# HenHouseController.net
KiCad netlist of a schematic drawn in EAGLE
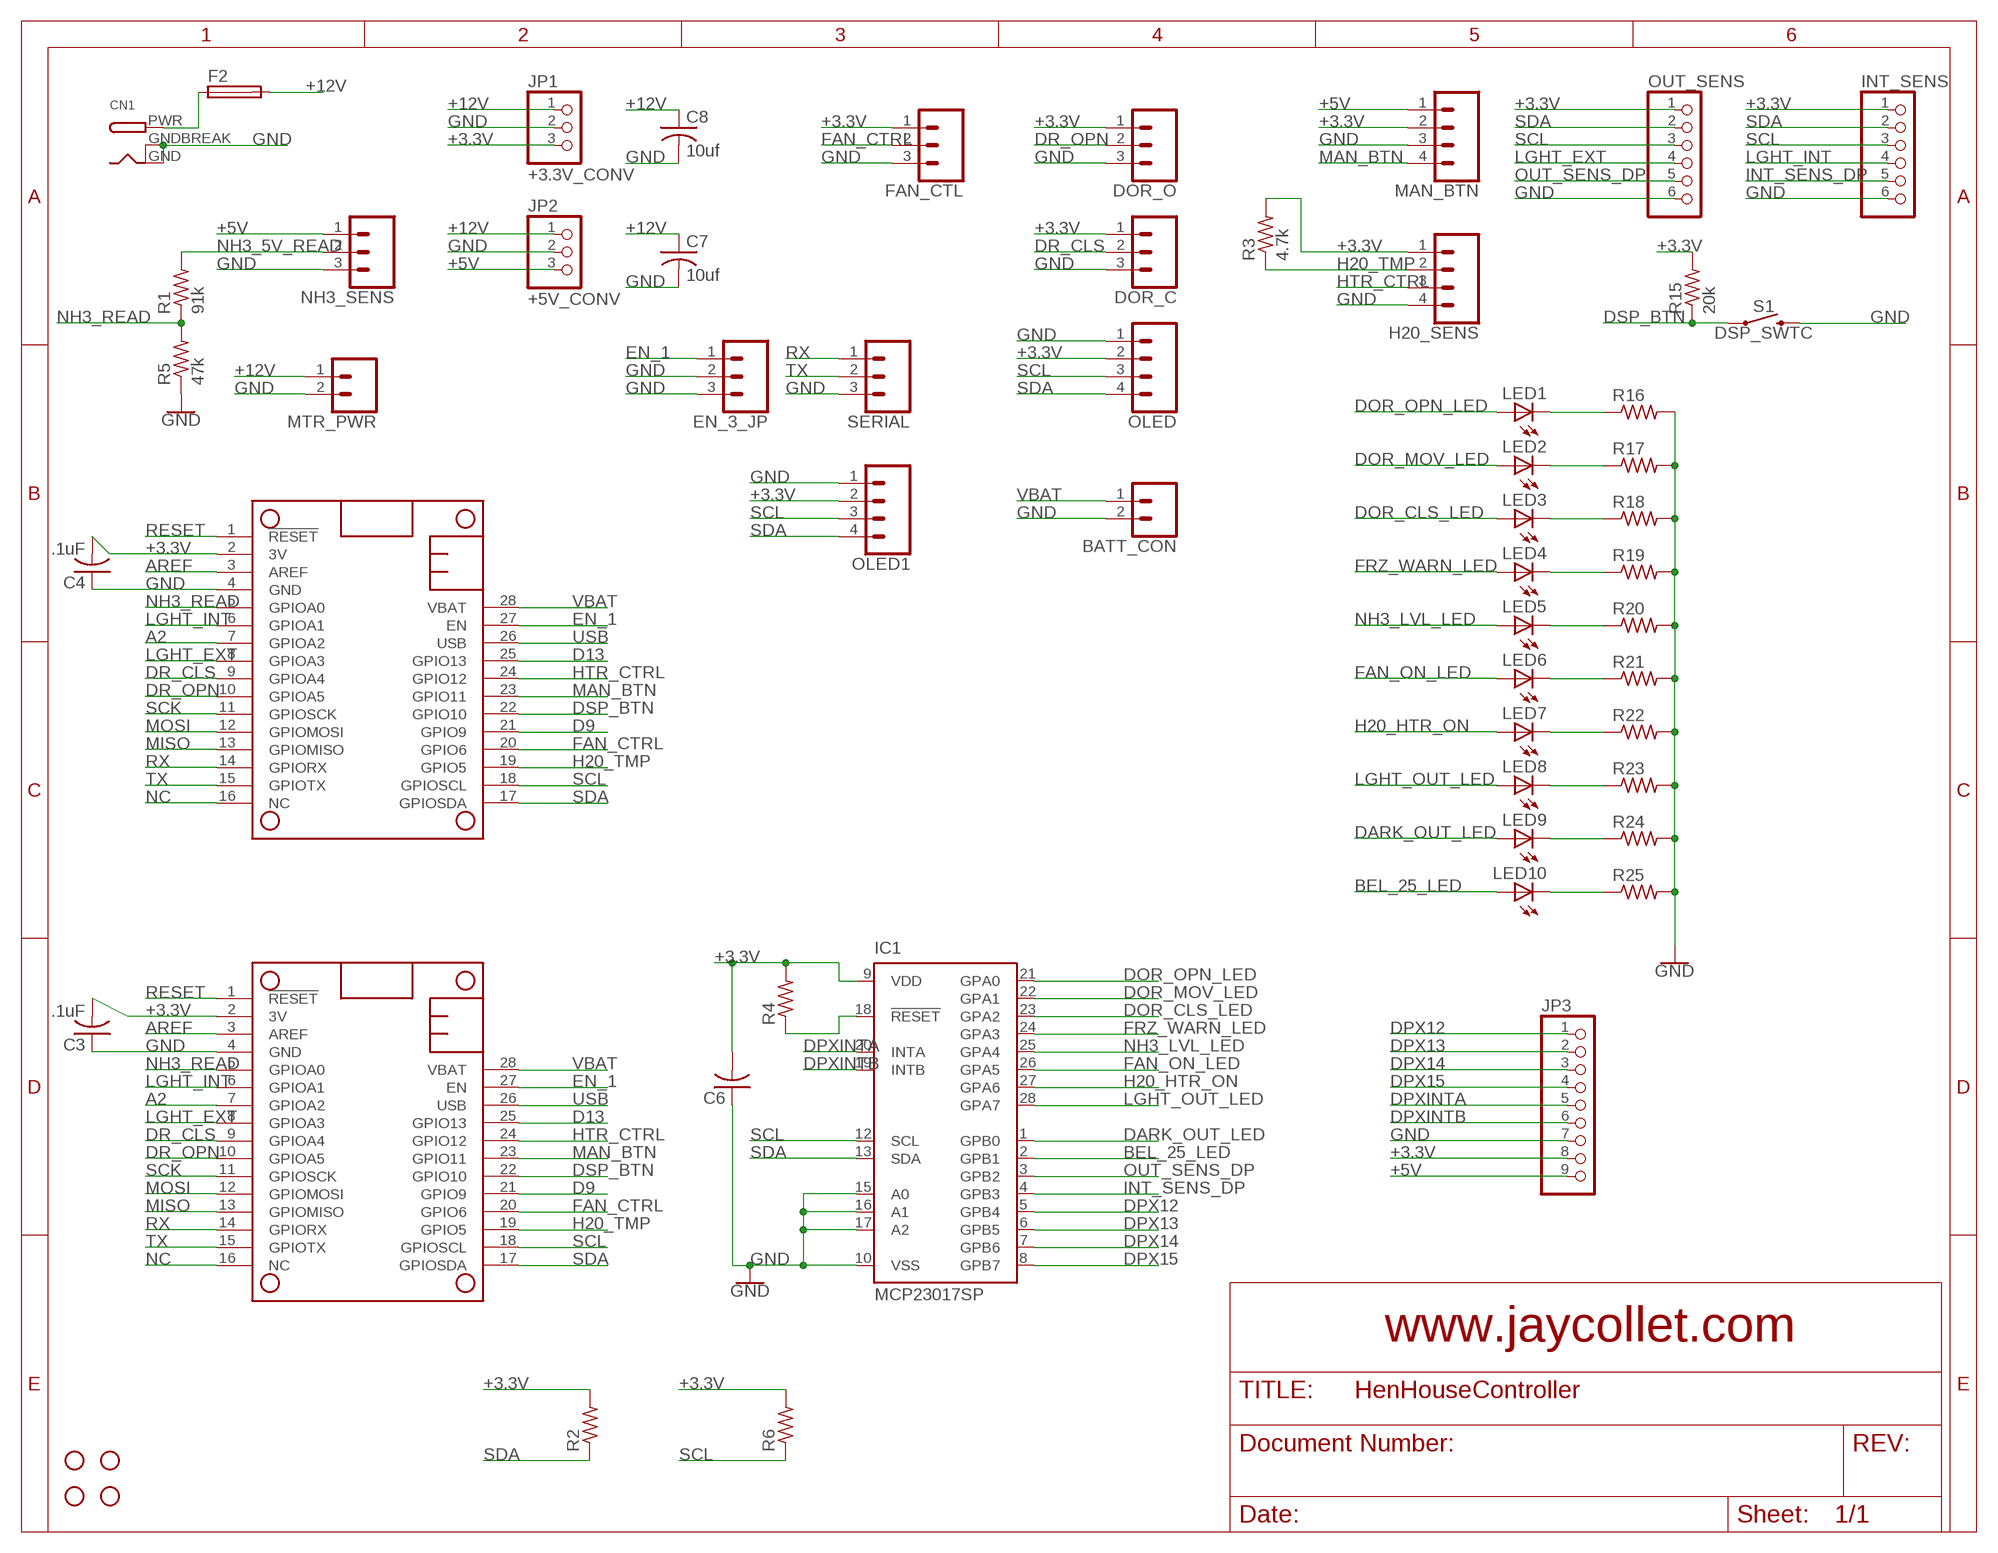
[diagram p0: schematic, sheet 1]

(export (version "E")
  (design (tool "Eeschema 10.0.6"))
  (components
    (comp (ref "BATT_CON")
      (value "CONN_02")
      (footprint "eagle-import:1X02")
      (libsource (lib "eagle-import") (part "CONN_02"))
    )
    (comp (ref "C3")
      (value ".1uF")
      (footprint "eagle-import:C0805")
      (libsource (lib "eagle-import") (part "C-USC0805"))
    )
    (comp (ref "C4")
      (value ".1uF")
      (footprint "eagle-import:C0805")
      (libsource (lib "eagle-import") (part "C-USC0805"))
    )
    (comp (ref "C6")
      (value "C-USC0805")
      (footprint "eagle-import:C0805")
      (libsource (lib "eagle-import") (part "C-USC0805"))
    )
    (comp (ref "C7")
      (value "10uf")
      (footprint "eagle-import:C0805")
      (libsource (lib "eagle-import") (part "C-USC0805"))
    )
    (comp (ref "C8")
      (value "10uf")
      (footprint "eagle-import:C0805")
      (libsource (lib "eagle-import") (part "C-USC0805"))
    )
    (comp (ref "CN1")
      (value "DCBARRELPTH")
      (footprint "eagle-import:DCJACK_2MM_PTH")
      (libsource (lib "eagle-import") (part "DCBARRELPTH"))
    )
    (comp (ref "DOR_C")
      (value "CONN_03")
      (footprint "eagle-import:1X03")
      (libsource (lib "eagle-import") (part "CONN_03"))
    )
    (comp (ref "DOR_O")
      (value "CONN_03")
      (footprint "eagle-import:1X03")
      (libsource (lib "eagle-import") (part "CONN_03"))
    )
    (comp (ref "EN_3_JP")
      (value "CONN_03")
      (footprint "eagle-import:1X03")
      (libsource (lib "eagle-import") (part "CONN_03"))
    )
    (comp (ref "F2")
      (value "SH25")
      (footprint "eagle-import:SH25")
      (fields (field (name "MF") "SCHURTER") (field (name "MPN") "0031.8211"))
      (libsource (lib "eagle-import") (part "SH25"))
    )
    (comp (ref "FAN_CTL")
      (value "CONN_03")
      (footprint "eagle-import:1X03")
      (libsource (lib "eagle-import") (part "CONN_03"))
    )
    (comp (ref "FEATHER_1")
      (value "FEATHERWING_NODIM")
      (footprint "eagle-import:FEATHERWING_DIM")
      (libsource (lib "eagle-import") (part "FEATHERWING_NODIM"))
    )
    (comp (ref "FEATHER_2")
      (value "FEATHERWING_NODIM")
      (footprint "eagle-import:FEATHERWING_DIM")
      (libsource (lib "eagle-import") (part "FEATHERWING_NODIM"))
    )
    (comp (ref "H1")
      (value "STAND-OFF")
      (footprint "eagle-import:STAND-OFF")
      (libsource (lib "eagle-import") (part "STAND-OFF"))
    )
    (comp (ref "H2")
      (value "STAND-OFF")
      (footprint "eagle-import:STAND-OFF")
      (libsource (lib "eagle-import") (part "STAND-OFF"))
    )
    (comp (ref "H3")
      (value "STAND-OFF")
      (footprint "eagle-import:STAND-OFF")
      (libsource (lib "eagle-import") (part "STAND-OFF"))
    )
    (comp (ref "H4")
      (value "STAND-OFF")
      (footprint "eagle-import:STAND-OFF")
      (libsource (lib "eagle-import") (part "STAND-OFF"))
    )
    (comp (ref "H20_SENS")
      (value "CONN_04")
      (footprint "eagle-import:1X04")
      (libsource (lib "eagle-import") (part "CONN_04"))
    )
    (comp (ref "IC1")
      (value "MCP23017SP")
      (footprint "eagle-import:DIL28-3")
      (libsource (lib "eagle-import") (part "MCP23017SP"))
    )
    (comp (ref "INT_SENS")
      (value "PINHD-1X6")
      (footprint "eagle-import:1X06")
      (libsource (lib "eagle-import") (part "PINHD-1X6"))
    )
    (comp (ref "JP1")
      (value "+3.3V_CONV")
      (footprint "eagle-import:1X03")
      (libsource (lib "eagle-import") (part "PINHD-1X3"))
    )
    (comp (ref "JP2")
      (value "+5V_CONV")
      (footprint "eagle-import:1X03")
      (libsource (lib "eagle-import") (part "PINHD-1X3"))
    )
    (comp (ref "JP3")
      (value "PINHD-1X9")
      (footprint "eagle-import:1X09-BIG")
      (libsource (lib "eagle-import") (part "PINHD-1X9"))
    )
    (comp (ref "LED1")
      (value "LEDCHIPLED_0805")
      (footprint "eagle-import:CHIPLED_0805")
      (libsource (lib "eagle-import") (part "LEDCHIPLED_0805"))
    )
    (comp (ref "LED2")
      (value "LEDCHIPLED_0805")
      (footprint "eagle-import:CHIPLED_0805")
      (libsource (lib "eagle-import") (part "LEDCHIPLED_0805"))
    )
    (comp (ref "LED3")
      (value "LEDCHIPLED_0805")
      (footprint "eagle-import:CHIPLED_0805")
      (libsource (lib "eagle-import") (part "LEDCHIPLED_0805"))
    )
    (comp (ref "LED4")
      (value "LEDCHIPLED_0805")
      (footprint "eagle-import:CHIPLED_0805")
      (libsource (lib "eagle-import") (part "LEDCHIPLED_0805"))
    )
    (comp (ref "LED5")
      (value "LEDCHIPLED_0805")
      (footprint "eagle-import:CHIPLED_0805")
      (libsource (lib "eagle-import") (part "LEDCHIPLED_0805"))
    )
    (comp (ref "LED6")
      (value "LEDCHIPLED_0805")
      (footprint "eagle-import:CHIPLED_0805")
      (libsource (lib "eagle-import") (part "LEDCHIPLED_0805"))
    )
    (comp (ref "LED7")
      (value "LEDCHIPLED_0805")
      (footprint "eagle-import:CHIPLED_0805")
      (libsource (lib "eagle-import") (part "LEDCHIPLED_0805"))
    )
    (comp (ref "LED8")
      (value "LEDCHIPLED_0805")
      (footprint "eagle-import:CHIPLED_0805")
      (libsource (lib "eagle-import") (part "LEDCHIPLED_0805"))
    )
    (comp (ref "LED9")
      (value "LEDCHIPLED_0805")
      (footprint "eagle-import:CHIPLED_0805")
      (libsource (lib "eagle-import") (part "LEDCHIPLED_0805"))
    )
    (comp (ref "LED10")
      (value "LEDCHIPLED_0805")
      (footprint "eagle-import:CHIPLED_0805")
      (libsource (lib "eagle-import") (part "LEDCHIPLED_0805"))
    )
    (comp (ref "MAN_BTN")
      (value "CONN_04")
      (footprint "eagle-import:1X04")
      (libsource (lib "eagle-import") (part "CONN_04"))
    )
    (comp (ref "MTR_PWR")
      (value "CONN_02")
      (footprint "eagle-import:1X02")
      (libsource (lib "eagle-import") (part "CONN_02"))
    )
    (comp (ref "NH3_SENS")
      (value "CONN_03")
      (footprint "eagle-import:1X03")
      (libsource (lib "eagle-import") (part "CONN_03"))
    )
    (comp (ref "OLED")
      (value "CONN_04")
      (footprint "eagle-import:1X04")
      (libsource (lib "eagle-import") (part "CONN_04"))
    )
    (comp (ref "OLED1")
      (value "CONN_04")
      (footprint "eagle-import:1X04")
      (libsource (lib "eagle-import") (part "CONN_04"))
    )
    (comp (ref "OUT_SENS")
      (value "PINHD-1X6")
      (footprint "eagle-import:1X06")
      (libsource (lib "eagle-import") (part "PINHD-1X6"))
    )
    (comp (ref "R1")
      (value "91k")
      (footprint "eagle-import:R0805")
      (libsource (lib "eagle-import") (part "R-US_R0805"))
    )
    (comp (ref "R2")
      (value "R-US_M0805")
      (footprint "eagle-import:M0805")
      (libsource (lib "eagle-import") (part "R-US_M0805"))
    )
    (comp (ref "R3")
      (value "4.7k")
      (footprint "eagle-import:R0805")
      (libsource (lib "eagle-import") (part "R-US_R0805"))
    )
    (comp (ref "R4")
      (value "R-US_R0805")
      (footprint "eagle-import:R0805")
      (libsource (lib "eagle-import") (part "R-US_R0805"))
    )
    (comp (ref "R5")
      (value "47k")
      (footprint "eagle-import:R0805")
      (libsource (lib "eagle-import") (part "R-US_R0805"))
    )
    (comp (ref "R6")
      (value "R-US_M0805")
      (footprint "eagle-import:M0805")
      (libsource (lib "eagle-import") (part "R-US_M0805"))
    )
    (comp (ref "R15")
      (value "20k")
      (footprint "eagle-import:M0805")
      (libsource (lib "eagle-import") (part "R-US_M0805"))
    )
    (comp (ref "R16")
      (value "R-US_R0805")
      (footprint "eagle-import:R0805")
      (libsource (lib "eagle-import") (part "R-US_R0805"))
    )
    (comp (ref "R17")
      (value "R-US_R0805")
      (footprint "eagle-import:R0805")
      (libsource (lib "eagle-import") (part "R-US_R0805"))
    )
    (comp (ref "R18")
      (value "R-US_R0805")
      (footprint "eagle-import:R0805")
      (libsource (lib "eagle-import") (part "R-US_R0805"))
    )
    (comp (ref "R19")
      (value "R-US_R0805")
      (footprint "eagle-import:R0805")
      (libsource (lib "eagle-import") (part "R-US_R0805"))
    )
    (comp (ref "R20")
      (value "R-US_R0805")
      (footprint "eagle-import:R0805")
      (libsource (lib "eagle-import") (part "R-US_R0805"))
    )
    (comp (ref "R21")
      (value "R-US_R0805")
      (footprint "eagle-import:R0805")
      (libsource (lib "eagle-import") (part "R-US_R0805"))
    )
    (comp (ref "R22")
      (value "R-US_R0805")
      (footprint "eagle-import:R0805")
      (libsource (lib "eagle-import") (part "R-US_R0805"))
    )
    (comp (ref "R23")
      (value "R-US_R0805")
      (footprint "eagle-import:R0805")
      (libsource (lib "eagle-import") (part "R-US_R0805"))
    )
    (comp (ref "R24")
      (value "R-US_R0805")
      (footprint "eagle-import:R0805")
      (libsource (lib "eagle-import") (part "R-US_R0805"))
    )
    (comp (ref "R25")
      (value "R-US_R0805")
      (footprint "eagle-import:R0805")
      (libsource (lib "eagle-import") (part "R-US_R0805"))
    )
    (comp (ref "S1")
      (value "DSP_SWTC")
      (footprint "eagle-import:TACTILE_SWITCH_PTH_6.0MM")
      (libsource (lib "eagle-import") (part "MOMENTARY-SWITCH-SPST-PTH-6.0MM"))
    )
    (comp (ref "SERIAL")
      (value "CONN_03")
      (footprint "eagle-import:1X03")
      (libsource (lib "eagle-import") (part "CONN_03"))
    )
  )
  (nets
    (net (code "1") (name "/+3.3V") (class "Default")
      (node (ref "C3") (pin "2") (pinfunction "2_2") (pintype "passive"))
      (node (ref "C4") (pin "2") (pinfunction "2_2") (pintype "passive"))
      (node (ref "C6") (pin "2") (pinfunction "2_2") (pintype "passive"))
      (node (ref "DOR_C") (pin "1") (pinfunction "1_1") (pintype "passive"))
      (node (ref "DOR_O") (pin "1") (pinfunction "1_1") (pintype "passive"))
      (node (ref "FAN_CTL") (pin "1") (pinfunction "1_1") (pintype "passive"))
      (node (ref "FEATHER_1") (pin "2") (pinfunction "3V_2") (pintype "power_in"))
      (node (ref "FEATHER_2") (pin "2") (pinfunction "3V_2") (pintype "power_in"))
      (node (ref "H20_SENS") (pin "1") (pinfunction "1_1") (pintype "passive"))
      (node (ref "IC1") (pin "9") (pinfunction "VDD_9") (pintype "power_in"))
      (node (ref "INT_SENS") (pin "1") (pinfunction "1_1") (pintype "passive"))
      (node (ref "JP1") (pin "3") (pinfunction "3_3") (pintype "passive"))
      (node (ref "JP3") (pin "8") (pinfunction "8_8") (pintype "passive"))
      (node (ref "MAN_BTN") (pin "2") (pinfunction "2_2") (pintype "passive"))
      (node (ref "OLED") (pin "2") (pinfunction "2_2") (pintype "passive"))
      (node (ref "OLED1") (pin "2") (pinfunction "2_2") (pintype "passive"))
      (node (ref "OUT_SENS") (pin "1") (pinfunction "1_1") (pintype "passive"))
      (node (ref "R15") (pin "2") (pinfunction "2_2") (pintype "passive"))
      (node (ref "R2") (pin "2") (pinfunction "2_2") (pintype "passive"))
      (node (ref "R3") (pin "2") (pinfunction "2_2") (pintype "passive"))
      (node (ref "R4") (pin "2") (pinfunction "2_2") (pintype "passive"))
      (node (ref "R6") (pin "2") (pinfunction "2_2") (pintype "passive"))
    )
    (net (code "2") (name "/+5V") (class "Default")
      (node (ref "JP2") (pin "3") (pinfunction "3_3") (pintype "passive"))
      (node (ref "JP3") (pin "9") (pinfunction "9_9") (pintype "passive"))
      (node (ref "MAN_BTN") (pin "1") (pinfunction "1_1") (pintype "passive"))
      (node (ref "NH3_SENS") (pin "1") (pinfunction "1_1") (pintype "passive"))
    )
    (net (code "3") (name "/+12V") (class "Default")
      (node (ref "C7") (pin "1") (pinfunction "1_1") (pintype "passive"))
      (node (ref "C8") (pin "1") (pinfunction "1_1") (pintype "passive"))
      (node (ref "F2") (pin "2") (pinfunction "2_2") (pintype "passive"))
      (node (ref "JP1") (pin "1") (pinfunction "1_1") (pintype "passive"))
      (node (ref "JP2") (pin "1") (pinfunction "1_1") (pintype "passive"))
      (node (ref "MTR_PWR") (pin "1") (pinfunction "1_1") (pintype "passive"))
    )
    (net (code "4") (name "/A2") (class "Default")
      (node (ref "FEATHER_1") (pin "7") (pinfunction "GPIOA2_7") (pintype "bidirectional"))
      (node (ref "FEATHER_2") (pin "7") (pinfunction "GPIOA2_7") (pintype "bidirectional"))
    )
    (net (code "5") (name "/AREF") (class "Default")
      (node (ref "FEATHER_1") (pin "3") (pinfunction "AREF_3") (pintype "passive"))
      (node (ref "FEATHER_2") (pin "3") (pinfunction "AREF_3") (pintype "passive"))
    )
    (net (code "6") (name "/BEL_25_LED") (class "Default")
      (node (ref "IC1") (pin "2") (pinfunction "GPB1_2") (pintype "bidirectional"))
      (node (ref "LED10") (pin "A") (pinfunction "A_A") (pintype "passive"))
    )
    (net (code "7") (name "/D9") (class "Default")
      (node (ref "FEATHER_1") (pin "21") (pinfunction "GPIO9_21") (pintype "bidirectional"))
      (node (ref "FEATHER_2") (pin "21") (pinfunction "GPIO9_21") (pintype "bidirectional"))
    )
    (net (code "8") (name "/D13") (class "Default")
      (node (ref "FEATHER_1") (pin "25") (pinfunction "GPIO13_25") (pintype "bidirectional"))
      (node (ref "FEATHER_2") (pin "25") (pinfunction "GPIO13_25") (pintype "bidirectional"))
    )
    (net (code "9") (name "/DARK_OUT_LED") (class "Default")
      (node (ref "IC1") (pin "1") (pinfunction "GPB0_1") (pintype "bidirectional"))
      (node (ref "LED9") (pin "A") (pinfunction "A_A") (pintype "passive"))
    )
    (net (code "10") (name "/DOR_CLS_LED") (class "Default")
      (node (ref "IC1") (pin "23") (pinfunction "GPA2_23") (pintype "bidirectional"))
      (node (ref "LED3") (pin "A") (pinfunction "A_A") (pintype "passive"))
    )
    (net (code "11") (name "/DOR_MOV_LED") (class "Default")
      (node (ref "IC1") (pin "22") (pinfunction "GPA1_22") (pintype "bidirectional"))
      (node (ref "LED2") (pin "A") (pinfunction "A_A") (pintype "passive"))
    )
    (net (code "12") (name "/DOR_OPN_LED") (class "Default")
      (node (ref "IC1") (pin "21") (pinfunction "GPA0_21") (pintype "bidirectional"))
      (node (ref "LED1") (pin "A") (pinfunction "A_A") (pintype "passive"))
    )
    (net (code "13") (name "/DPX12") (class "Default")
      (node (ref "IC1") (pin "5") (pinfunction "GPB4_5") (pintype "bidirectional"))
      (node (ref "JP3") (pin "1") (pinfunction "1_1") (pintype "passive"))
    )
    (net (code "14") (name "/DPX13") (class "Default")
      (node (ref "IC1") (pin "6") (pinfunction "GPB5_6") (pintype "bidirectional"))
      (node (ref "JP3") (pin "2") (pinfunction "2_2") (pintype "passive"))
    )
    (net (code "15") (name "/DPX14") (class "Default")
      (node (ref "IC1") (pin "7") (pinfunction "GPB6_7") (pintype "bidirectional"))
      (node (ref "JP3") (pin "3") (pinfunction "3_3") (pintype "passive"))
    )
    (net (code "16") (name "/DPX15") (class "Default")
      (node (ref "IC1") (pin "8") (pinfunction "GPB7_8") (pintype "bidirectional"))
      (node (ref "JP3") (pin "4") (pinfunction "4_4") (pintype "passive"))
    )
    (net (code "17") (name "/DPXINTA") (class "Default")
      (node (ref "IC1") (pin "20") (pinfunction "INTA_20") (pintype "output"))
      (node (ref "JP3") (pin "5") (pinfunction "5_5") (pintype "passive"))
    )
    (net (code "18") (name "/DPXINTB") (class "Default")
      (node (ref "IC1") (pin "19") (pinfunction "INTB_19") (pintype "output"))
      (node (ref "JP3") (pin "6") (pinfunction "6_6") (pintype "passive"))
    )
    (net (code "19") (name "/DR_CLS") (class "Default")
      (node (ref "DOR_C") (pin "2") (pinfunction "2_2") (pintype "passive"))
      (node (ref "FEATHER_1") (pin "9") (pinfunction "GPIOA4_9") (pintype "bidirectional"))
      (node (ref "FEATHER_2") (pin "9") (pinfunction "GPIOA4_9") (pintype "bidirectional"))
    )
    (net (code "20") (name "/DR_OPN") (class "Default")
      (node (ref "DOR_O") (pin "2") (pinfunction "2_2") (pintype "passive"))
      (node (ref "FEATHER_1") (pin "10") (pinfunction "GPIOA5_10") (pintype "bidirectional"))
      (node (ref "FEATHER_2") (pin "10") (pinfunction "GPIOA5_10") (pintype "bidirectional"))
    )
    (net (code "21") (name "/DSP_BTN") (class "Default")
      (node (ref "FEATHER_1") (pin "22") (pinfunction "GPIO10_22") (pintype "bidirectional"))
      (node (ref "FEATHER_2") (pin "22") (pinfunction "GPIO10_22") (pintype "bidirectional"))
      (node (ref "R15") (pin "1") (pinfunction "1_1") (pintype "passive"))
      (node (ref "S1") (pin "1") (pinfunction "1_1") (pintype "passive"))
    )
    (net (code "22") (name "/EN_1") (class "Default")
      (node (ref "EN_3_JP") (pin "1") (pinfunction "1_1") (pintype "passive"))
      (node (ref "FEATHER_1") (pin "27") (pinfunction "EN_27") (pintype "passive"))
      (node (ref "FEATHER_2") (pin "27") (pinfunction "EN_27") (pintype "passive"))
    )
    (net (code "23") (name "/FAN_CTRL") (class "Default")
      (node (ref "FAN_CTL") (pin "2") (pinfunction "2_2") (pintype "passive"))
      (node (ref "FEATHER_1") (pin "20") (pinfunction "GPIO6_20") (pintype "bidirectional"))
      (node (ref "FEATHER_2") (pin "20") (pinfunction "GPIO6_20") (pintype "bidirectional"))
    )
    (net (code "24") (name "/FAN_ON_LED") (class "Default")
      (node (ref "IC1") (pin "26") (pinfunction "GPA5_26") (pintype "bidirectional"))
      (node (ref "LED6") (pin "A") (pinfunction "A_A") (pintype "passive"))
    )
    (net (code "25") (name "/FRZ_WARN_LED") (class "Default")
      (node (ref "IC1") (pin "24") (pinfunction "GPA3_24") (pintype "bidirectional"))
      (node (ref "LED4") (pin "A") (pinfunction "A_A") (pintype "passive"))
    )
    (net (code "26") (name "/H20_HTR_ON") (class "Default")
      (node (ref "IC1") (pin "27") (pinfunction "GPA6_27") (pintype "bidirectional"))
      (node (ref "LED7") (pin "A") (pinfunction "A_A") (pintype "passive"))
    )
    (net (code "27") (name "/H20_TMP") (class "Default")
      (node (ref "FEATHER_1") (pin "19") (pinfunction "GPIO5_19") (pintype "bidirectional"))
      (node (ref "FEATHER_2") (pin "19") (pinfunction "GPIO5_19") (pintype "bidirectional"))
      (node (ref "H20_SENS") (pin "2") (pinfunction "2_2") (pintype "passive"))
      (node (ref "R3") (pin "1") (pinfunction "1_1") (pintype "passive"))
    )
    (net (code "28") (name "/HTR_CTRL") (class "Default")
      (node (ref "FEATHER_1") (pin "24") (pinfunction "GPIO12_24") (pintype "bidirectional"))
      (node (ref "FEATHER_2") (pin "24") (pinfunction "GPIO12_24") (pintype "bidirectional"))
      (node (ref "H20_SENS") (pin "3") (pinfunction "3_3") (pintype "passive"))
    )
    (net (code "29") (name "/INT_SENS_DP") (class "Default")
      (node (ref "IC1") (pin "4") (pinfunction "GPB3_4") (pintype "bidirectional"))
      (node (ref "INT_SENS") (pin "5") (pinfunction "5_5") (pintype "passive"))
    )
    (net (code "30") (name "/LGHT_EXT") (class "Default")
      (node (ref "FEATHER_1") (pin "8") (pinfunction "GPIOA3_8") (pintype "bidirectional"))
      (node (ref "FEATHER_2") (pin "8") (pinfunction "GPIOA3_8") (pintype "bidirectional"))
      (node (ref "OUT_SENS") (pin "4") (pinfunction "4_4") (pintype "passive"))
    )
    (net (code "31") (name "/LGHT_INT") (class "Default")
      (node (ref "FEATHER_1") (pin "6") (pinfunction "GPIOA1_6") (pintype "bidirectional"))
      (node (ref "FEATHER_2") (pin "6") (pinfunction "GPIOA1_6") (pintype "bidirectional"))
      (node (ref "INT_SENS") (pin "4") (pinfunction "4_4") (pintype "passive"))
    )
    (net (code "32") (name "/LGHT_OUT_LED") (class "Default")
      (node (ref "IC1") (pin "28") (pinfunction "GPA7_28") (pintype "bidirectional"))
      (node (ref "LED8") (pin "A") (pinfunction "A_A") (pintype "passive"))
    )
    (net (code "33") (name "/MAN_BTN") (class "Default")
      (node (ref "FEATHER_1") (pin "23") (pinfunction "GPIO11_23") (pintype "bidirectional"))
      (node (ref "FEATHER_2") (pin "23") (pinfunction "GPIO11_23") (pintype "bidirectional"))
      (node (ref "MAN_BTN") (pin "4") (pinfunction "4_4") (pintype "passive"))
    )
    (net (code "34") (name "/MISO") (class "Default")
      (node (ref "FEATHER_1") (pin "13") (pinfunction "GPIOMISO_13") (pintype "bidirectional"))
      (node (ref "FEATHER_2") (pin "13") (pinfunction "GPIOMISO_13") (pintype "bidirectional"))
    )
    (net (code "35") (name "/MOSI") (class "Default")
      (node (ref "FEATHER_1") (pin "12") (pinfunction "GPIOMOSI_12") (pintype "bidirectional"))
      (node (ref "FEATHER_2") (pin "12") (pinfunction "GPIOMOSI_12") (pintype "bidirectional"))
    )
    (net (code "36") (name "/NC") (class "Default")
      (node (ref "FEATHER_1") (pin "16") (pinfunction "NC_16") (pintype "passive"))
      (node (ref "FEATHER_2") (pin "16") (pinfunction "NC_16") (pintype "passive"))
    )
    (net (code "37") (name "/NH3_5V_READ") (class "Default")
      (node (ref "NH3_SENS") (pin "2") (pinfunction "2_2") (pintype "passive"))
      (node (ref "R1") (pin "2") (pinfunction "2_2") (pintype "passive"))
    )
    (net (code "38") (name "/NH3_LVL_LED") (class "Default")
      (node (ref "IC1") (pin "25") (pinfunction "GPA4_25") (pintype "bidirectional"))
      (node (ref "LED5") (pin "A") (pinfunction "A_A") (pintype "passive"))
    )
    (net (code "39") (name "/NH3_READ") (class "Default")
      (node (ref "FEATHER_1") (pin "5") (pinfunction "GPIOA0_5") (pintype "bidirectional"))
      (node (ref "FEATHER_2") (pin "5") (pinfunction "GPIOA0_5") (pintype "bidirectional"))
      (node (ref "R1") (pin "1") (pinfunction "1_1") (pintype "passive"))
      (node (ref "R5") (pin "2") (pinfunction "2_2") (pintype "passive"))
    )
    (net (code "40") (name "/OUT_SENS_DP") (class "Default")
      (node (ref "IC1") (pin "3") (pinfunction "GPB2_3") (pintype "bidirectional"))
      (node (ref "OUT_SENS") (pin "5") (pinfunction "5_5") (pintype "passive"))
    )
    (net (code "41") (name "/RESET") (class "Default")
      (node (ref "FEATHER_1") (pin "1") (pinfunction "~{RESET}_1") (pintype "input"))
      (node (ref "FEATHER_2") (pin "1") (pinfunction "~{RESET}_1") (pintype "input"))
    )
    (net (code "42") (name "/RX") (class "Default")
      (node (ref "FEATHER_1") (pin "14") (pinfunction "GPIORX_14") (pintype "bidirectional"))
      (node (ref "FEATHER_2") (pin "14") (pinfunction "GPIORX_14") (pintype "bidirectional"))
      (node (ref "SERIAL") (pin "1") (pinfunction "1_1") (pintype "passive"))
    )
    (net (code "43") (name "/SCK") (class "Default")
      (node (ref "FEATHER_1") (pin "11") (pinfunction "GPIOSCK_11") (pintype "bidirectional"))
      (node (ref "FEATHER_2") (pin "11") (pinfunction "GPIOSCK_11") (pintype "bidirectional"))
    )
    (net (code "44") (name "/SCL") (class "Default")
      (node (ref "FEATHER_1") (pin "18") (pinfunction "GPIOSCL_18") (pintype "bidirectional"))
      (node (ref "FEATHER_2") (pin "18") (pinfunction "GPIOSCL_18") (pintype "bidirectional"))
      (node (ref "IC1") (pin "12") (pinfunction "SCL_12") (pintype "input"))
      (node (ref "INT_SENS") (pin "3") (pinfunction "3_3") (pintype "passive"))
      (node (ref "OLED") (pin "3") (pinfunction "3_3") (pintype "passive"))
      (node (ref "OLED1") (pin "3") (pinfunction "3_3") (pintype "passive"))
      (node (ref "OUT_SENS") (pin "3") (pinfunction "3_3") (pintype "passive"))
      (node (ref "R6") (pin "1") (pinfunction "1_1") (pintype "passive"))
    )
    (net (code "45") (name "/SDA") (class "Default")
      (node (ref "FEATHER_1") (pin "17") (pinfunction "GPIOSDA_17") (pintype "bidirectional"))
      (node (ref "FEATHER_2") (pin "17") (pinfunction "GPIOSDA_17") (pintype "bidirectional"))
      (node (ref "IC1") (pin "13") (pinfunction "SDA_13") (pintype "bidirectional"))
      (node (ref "INT_SENS") (pin "2") (pinfunction "2_2") (pintype "passive"))
      (node (ref "OLED") (pin "4") (pinfunction "4_4") (pintype "passive"))
      (node (ref "OLED1") (pin "4") (pinfunction "4_4") (pintype "passive"))
      (node (ref "OUT_SENS") (pin "2") (pinfunction "2_2") (pintype "passive"))
      (node (ref "R2") (pin "1") (pinfunction "1_1") (pintype "passive"))
    )
    (net (code "46") (name "/TX") (class "Default")
      (node (ref "FEATHER_1") (pin "15") (pinfunction "GPIOTX_15") (pintype "bidirectional"))
      (node (ref "FEATHER_2") (pin "15") (pinfunction "GPIOTX_15") (pintype "bidirectional"))
      (node (ref "SERIAL") (pin "2") (pinfunction "2_2") (pintype "passive"))
    )
    (net (code "47") (name "/USB") (class "Default")
      (node (ref "FEATHER_1") (pin "26") (pinfunction "USB_26") (pintype "power_in"))
      (node (ref "FEATHER_2") (pin "26") (pinfunction "USB_26") (pintype "power_in"))
    )
    (net (code "48") (name "/VBAT") (class "Default")
      (node (ref "BATT_CON") (pin "1") (pinfunction "1_1") (pintype "passive"))
      (node (ref "FEATHER_1") (pin "28") (pinfunction "VBAT_28") (pintype "power_in"))
      (node (ref "FEATHER_2") (pin "28") (pinfunction "VBAT_28") (pintype "power_in"))
    )
    (net (code "49") (name "GND") (class "Default")
      (node (ref "BATT_CON") (pin "2") (pinfunction "2_2") (pintype "passive"))
      (node (ref "C3") (pin "1") (pinfunction "1_1") (pintype "passive"))
      (node (ref "C4") (pin "1") (pinfunction "1_1") (pintype "passive"))
      (node (ref "C6") (pin "1") (pinfunction "1_1") (pintype "passive"))
      (node (ref "C7") (pin "2") (pinfunction "2_2") (pintype "passive"))
      (node (ref "C8") (pin "2") (pinfunction "2_2") (pintype "passive"))
      (node (ref "CN1") (pin "GND") (pinfunction "GND_GND") (pintype "power_in"))
      (node (ref "CN1") (pin "GNDBREAK") (pinfunction "GNDBREAK_GNDBREAK") (pintype "power_in"))
      (node (ref "DOR_C") (pin "3") (pinfunction "3_3") (pintype "passive"))
      (node (ref "DOR_O") (pin "3") (pinfunction "3_3") (pintype "passive"))
      (node (ref "EN_3_JP") (pin "2") (pinfunction "2_2") (pintype "passive"))
      (node (ref "EN_3_JP") (pin "3") (pinfunction "3_3") (pintype "passive"))
      (node (ref "FAN_CTL") (pin "3") (pinfunction "3_3") (pintype "passive"))
      (node (ref "FEATHER_1") (pin "4") (pinfunction "GND_4") (pintype "power_in"))
      (node (ref "FEATHER_2") (pin "4") (pinfunction "GND_4") (pintype "power_in"))
      (node (ref "H20_SENS") (pin "4") (pinfunction "4_4") (pintype "passive"))
      (node (ref "IC1") (pin "10") (pinfunction "VSS_10") (pintype "power_in"))
      (node (ref "IC1") (pin "15") (pinfunction "A0_15") (pintype "input"))
      (node (ref "IC1") (pin "16") (pinfunction "A1_16") (pintype "input"))
      (node (ref "IC1") (pin "17") (pinfunction "A2_17") (pintype "input"))
      (node (ref "INT_SENS") (pin "6") (pinfunction "6_6") (pintype "passive"))
      (node (ref "JP1") (pin "2") (pinfunction "2_2") (pintype "passive"))
      (node (ref "JP2") (pin "2") (pinfunction "2_2") (pintype "passive"))
      (node (ref "JP3") (pin "7") (pinfunction "7_7") (pintype "passive"))
      (node (ref "MAN_BTN") (pin "3") (pinfunction "3_3") (pintype "passive"))
      (node (ref "MTR_PWR") (pin "2") (pinfunction "2_2") (pintype "passive"))
      (node (ref "NH3_SENS") (pin "3") (pinfunction "3_3") (pintype "passive"))
      (node (ref "OLED") (pin "1") (pinfunction "1_1") (pintype "passive"))
      (node (ref "OLED1") (pin "1") (pinfunction "1_1") (pintype "passive"))
      (node (ref "OUT_SENS") (pin "6") (pinfunction "6_6") (pintype "passive"))
      (node (ref "R16") (pin "2") (pinfunction "2_2") (pintype "passive"))
      (node (ref "R17") (pin "2") (pinfunction "2_2") (pintype "passive"))
      (node (ref "R18") (pin "2") (pinfunction "2_2") (pintype "passive"))
      (node (ref "R19") (pin "2") (pinfunction "2_2") (pintype "passive"))
      (node (ref "R20") (pin "2") (pinfunction "2_2") (pintype "passive"))
      (node (ref "R21") (pin "2") (pinfunction "2_2") (pintype "passive"))
      (node (ref "R22") (pin "2") (pinfunction "2_2") (pintype "passive"))
      (node (ref "R23") (pin "2") (pinfunction "2_2") (pintype "passive"))
      (node (ref "R24") (pin "2") (pinfunction "2_2") (pintype "passive"))
      (node (ref "R25") (pin "2") (pinfunction "2_2") (pintype "passive"))
      (node (ref "R5") (pin "1") (pinfunction "1_1") (pintype "passive"))
      (node (ref "S1") (pin "3") (pinfunction "2_3") (pintype "passive"))
      (node (ref "SERIAL") (pin "3") (pinfunction "3_3") (pintype "passive"))
    )
    (net (code "50") (name "Net-(CN1-PadPWR)") (class "Default")
      (node (ref "CN1") (pin "PWR") (pinfunction "PWR_PWR") (pintype "power_in"))
      (node (ref "F2") (pin "1") (pinfunction "1_1") (pintype "passive"))
    )
    (net (code "51") (name "Net-(IC1-~{RESET})") (class "Default")
      (node (ref "IC1") (pin "18") (pinfunction "~{RESET}_18") (pintype "input"))
      (node (ref "R4") (pin "1") (pinfunction "1_1") (pintype "passive"))
    )
    (net (code "52") (name "Net-(LED1-PadC)") (class "Default")
      (node (ref "LED1") (pin "C") (pinfunction "C_C") (pintype "passive"))
      (node (ref "R16") (pin "1") (pinfunction "1_1") (pintype "passive"))
    )
    (net (code "53") (name "Net-(LED2-PadC)") (class "Default")
      (node (ref "LED2") (pin "C") (pinfunction "C_C") (pintype "passive"))
      (node (ref "R17") (pin "1") (pinfunction "1_1") (pintype "passive"))
    )
    (net (code "54") (name "Net-(LED3-PadC)") (class "Default")
      (node (ref "LED3") (pin "C") (pinfunction "C_C") (pintype "passive"))
      (node (ref "R18") (pin "1") (pinfunction "1_1") (pintype "passive"))
    )
    (net (code "55") (name "Net-(LED4-PadC)") (class "Default")
      (node (ref "LED4") (pin "C") (pinfunction "C_C") (pintype "passive"))
      (node (ref "R19") (pin "1") (pinfunction "1_1") (pintype "passive"))
    )
    (net (code "56") (name "Net-(LED5-PadC)") (class "Default")
      (node (ref "LED5") (pin "C") (pinfunction "C_C") (pintype "passive"))
      (node (ref "R20") (pin "1") (pinfunction "1_1") (pintype "passive"))
    )
    (net (code "57") (name "Net-(LED6-PadC)") (class "Default")
      (node (ref "LED6") (pin "C") (pinfunction "C_C") (pintype "passive"))
      (node (ref "R21") (pin "1") (pinfunction "1_1") (pintype "passive"))
    )
    (net (code "58") (name "Net-(LED7-PadC)") (class "Default")
      (node (ref "LED7") (pin "C") (pinfunction "C_C") (pintype "passive"))
      (node (ref "R22") (pin "1") (pinfunction "1_1") (pintype "passive"))
    )
    (net (code "59") (name "Net-(LED8-PadC)") (class "Default")
      (node (ref "LED8") (pin "C") (pinfunction "C_C") (pintype "passive"))
      (node (ref "R23") (pin "1") (pinfunction "1_1") (pintype "passive"))
    )
    (net (code "60") (name "Net-(LED9-PadC)") (class "Default")
      (node (ref "LED9") (pin "C") (pinfunction "C_C") (pintype "passive"))
      (node (ref "R24") (pin "1") (pinfunction "1_1") (pintype "passive"))
    )
    (net (code "61") (name "Net-(LED10-PadC)") (class "Default")
      (node (ref "LED10") (pin "C") (pinfunction "C_C") (pintype "passive"))
      (node (ref "R25") (pin "1") (pinfunction "1_1") (pintype "passive"))
    )
  )
)
